# motor.net
KiCad netlist of a schematic drawn in Altium Designer
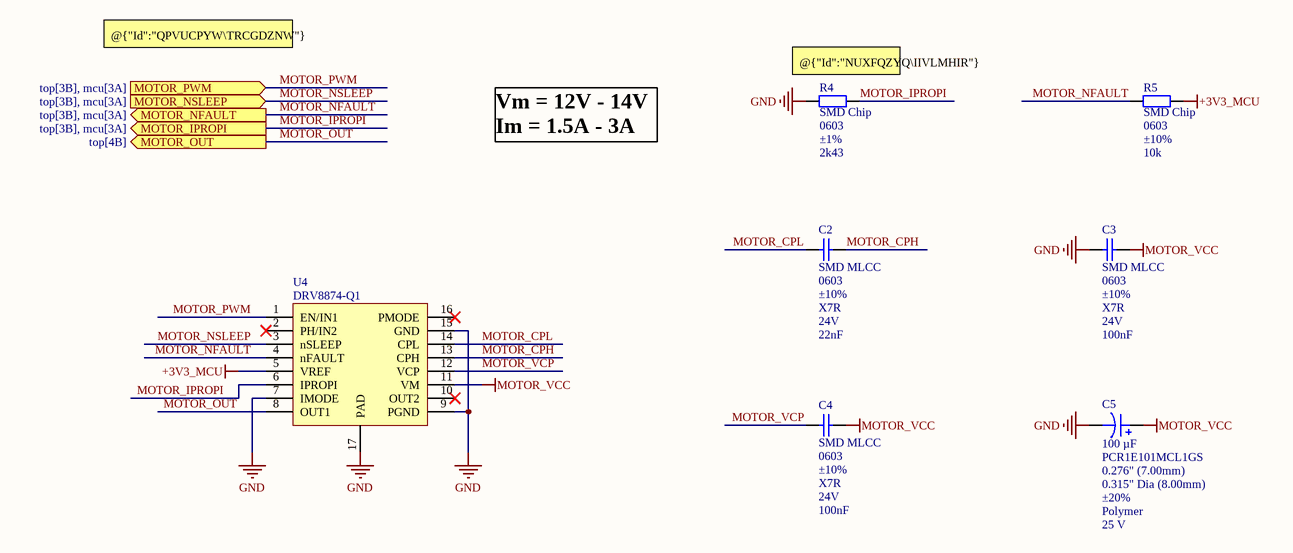
[diagram p0: motor.SchDoc]

(export (version "E")
  (design (tool "Eeschema 10.0.6"))
  (components
    (comp (ref "C2")
      (value "SMD MLCC")
      (footprint "SMD_MLCC_CAPACITOR_0603")
      (description "generic SMD MLCC capacitor")
      (fields
        (field (name "SIZE") "0603")
        (field (name "TOLERANCE") "±10%")
        (field (name "DIELECTRIC") "X7R")
        (field (name "VOLTAGERATING") "24V")
        (field (name "CAPACITANCE") "22nF")
      )
      (libsource (lib "altium_library") (part "SMD MLCC Capacitor"))
    )
    (comp (ref "C3")
      (value "SMD MLCC")
      (footprint "SMD_MLCC_CAPACITOR_0603")
      (description "generic SMD MLCC capacitor")
      (fields
        (field (name "SIZE") "0603")
        (field (name "TOLERANCE") "±10%")
        (field (name "DIELECTRIC") "X7R")
        (field (name "VOLTAGERATING") "24V")
        (field (name "CAPACITANCE") "100nF")
      )
      (libsource (lib "altium_library") (part "SMD MLCC Capacitor"))
    )
    (comp (ref "C4")
      (value "SMD MLCC")
      (footprint "SMD_MLCC_CAPACITOR_0603")
      (description "generic SMD MLCC capacitor")
      (fields
        (field (name "SIZE") "0603")
        (field (name "TOLERANCE") "±10%")
        (field (name "DIELECTRIC") "X7R")
        (field (name "VOLTAGERATING") "24V")
        (field (name "CAPACITANCE") "100nF")
      )
      (libsource (lib "altium_library") (part "SMD MLCC Capacitor"))
    )
    (comp (ref "C5")
      (value "100 µF")
      (footprint "CAP ALSMD POLY 8.3MM H7.0MM")
      (description "CAP ALUM POLY 100UF 20% 25V SMD")
      (fields
        (field (name "PART NUMBER") "PCR1E101MCL1GS")
        (field (name "HEIGHT - SEATED (MAX)") "0.276\" (7.00mm)")
        (field (name "MANUFACTURER") "Nichicon")
        (field (name "SIZE / DIMENSION") "0.315\" Dia (8.00mm)")
        (field (name "TOLERANCE") "±20%")
        (field (name "TYPE") "Polymer")
        (field (name "VOLTAGE - RATED") "25 V")
      )
      (libsource (lib "Celestial Altium Library - altium_library") (part "Polarised Capacitor"))
    )
    (comp (ref "R4")
      (value "SMD Chip")
      (footprint "SMD_CHIP_RESISTOR_0603")
      (description "generic SMD chip resistor")
      (fields
        (field (name "SIZE") "0603")
        (field (name "TOLERANCE") "±1%")
        (field (name "RESISTANCE") "2k43")
      )
      (libsource (lib "altium_library") (part "SMD Chip Resistor"))
    )
    (comp (ref "R5")
      (value "SMD Chip")
      (footprint "SMD_CHIP_RESISTOR_0603")
      (description "generic SMD chip resistor")
      (fields
        (field (name "SIZE") "0603")
        (field (name "TOLERANCE") "±10%")
        (field (name "RESISTANCE") "10k")
      )
      (libsource (lib "altium_library") (part "SMD Chip Resistor"))
    )
    (comp (ref "U4")
      (value "DRV8874-Q1")
      (footprint "DRV8874-Q1")
      (description "brushed DC motor driver")
      (libsource (lib "altium_library") (part "DRV8874-Q1"))
    )
  )
  (nets
    (net (code "1") (name "+3V3_MCU") (class "Default")
      (node (ref "R5") (pin "2") (pinfunction "2_2") (pintype "passive"))
      (node (ref "U4") (pin "5") (pinfunction "VREF_5") (pintype "passive"))
    )
    (net (code "2") (name "/MOTOR_CPH") (class "Default")
      (node (ref "C2") (pin "2") (pinfunction "2_2") (pintype "passive"))
      (node (ref "U4") (pin "13") (pinfunction "CPH_13") (pintype "passive"))
    )
    (net (code "3") (name "/MOTOR_CPL") (class "Default")
      (node (ref "C2") (pin "1") (pinfunction "1_1") (pintype "passive"))
      (node (ref "U4") (pin "14") (pinfunction "CPL_14") (pintype "passive"))
    )
    (net (code "4") (name "/MOTOR_IPROPI") (class "Default")
      (node (ref "R4") (pin "2") (pinfunction "2_2") (pintype "passive"))
      (node (ref "U4") (pin "6") (pinfunction "IPROPI_6") (pintype "passive"))
    )
    (net (code "5") (name "/MOTOR_NFAULT") (class "Default")
      (node (ref "R5") (pin "1") (pinfunction "1_1") (pintype "passive"))
      (node (ref "U4") (pin "4") (pinfunction "nFAULT_4") (pintype "passive"))
    )
    (net (code "6") (name "/MOTOR_NSLEEP") (class "Default")
      (node (ref "U4") (pin "3") (pinfunction "nSLEEP_3") (pintype "passive"))
    )
    (net (code "7") (name "/MOTOR_OUT") (class "Default")
      (node (ref "U4") (pin "8") (pinfunction "OUT1_8") (pintype "passive"))
    )
    (net (code "8") (name "/MOTOR_PWM") (class "Default")
      (node (ref "U4") (pin "1") (pinfunction "EN/IN1_1") (pintype "passive"))
    )
    (net (code "9") (name "/MOTOR_VCP") (class "Default")
      (node (ref "C4") (pin "1") (pinfunction "1_1") (pintype "passive"))
      (node (ref "U4") (pin "12") (pinfunction "VCP_12") (pintype "passive"))
    )
    (net (code "10") (name "GND") (class "Default")
      (node (ref "C3") (pin "2") (pinfunction "2_2") (pintype "passive"))
      (node (ref "C5") (pin "2") (pinfunction "2_2") (pintype "passive"))
      (node (ref "R4") (pin "1") (pinfunction "1_1") (pintype "passive"))
      (node (ref "U4") (pin "15") (pinfunction "GND_15") (pintype "passive"))
      (node (ref "U4") (pin "17") (pinfunction "PAD_17") (pintype "passive"))
      (node (ref "U4") (pin "7") (pinfunction "IMODE_7") (pintype "passive"))
      (node (ref "U4") (pin "9") (pinfunction "PGND_9") (pintype "passive"))
    )
    (net (code "11") (name "MOTOR_VCC") (class "Default")
      (node (ref "C3") (pin "1") (pinfunction "1_1") (pintype "passive"))
      (node (ref "C4") (pin "2") (pinfunction "2_2") (pintype "passive"))
      (node (ref "C5") (pin "1") (pinfunction "1_1") (pintype "passive"))
      (node (ref "U4") (pin "11") (pinfunction "VM_11") (pintype "passive"))
    )
    (net (code "12") (name "unconnected-(U4-OUT2-Pad10)") (class "Default")
      (node (ref "U4") (pin "10") (pinfunction "OUT2_10") (pintype "passive+no_connect"))
    )
    (net (code "13") (name "unconnected-(U4-PH{slash}IN2-Pad2)") (class "Default")
      (node (ref "U4") (pin "2") (pinfunction "PH/IN2_2") (pintype "passive+no_connect"))
    )
    (net (code "14") (name "unconnected-(U4-PMODE-Pad16)") (class "Default")
      (node (ref "U4") (pin "16") (pinfunction "PMODE_16") (pintype "passive+no_connect"))
    )
  )
)
